# PS2toUSB.net
KiCad netlist of a schematic drawn in EasyEDA Pro
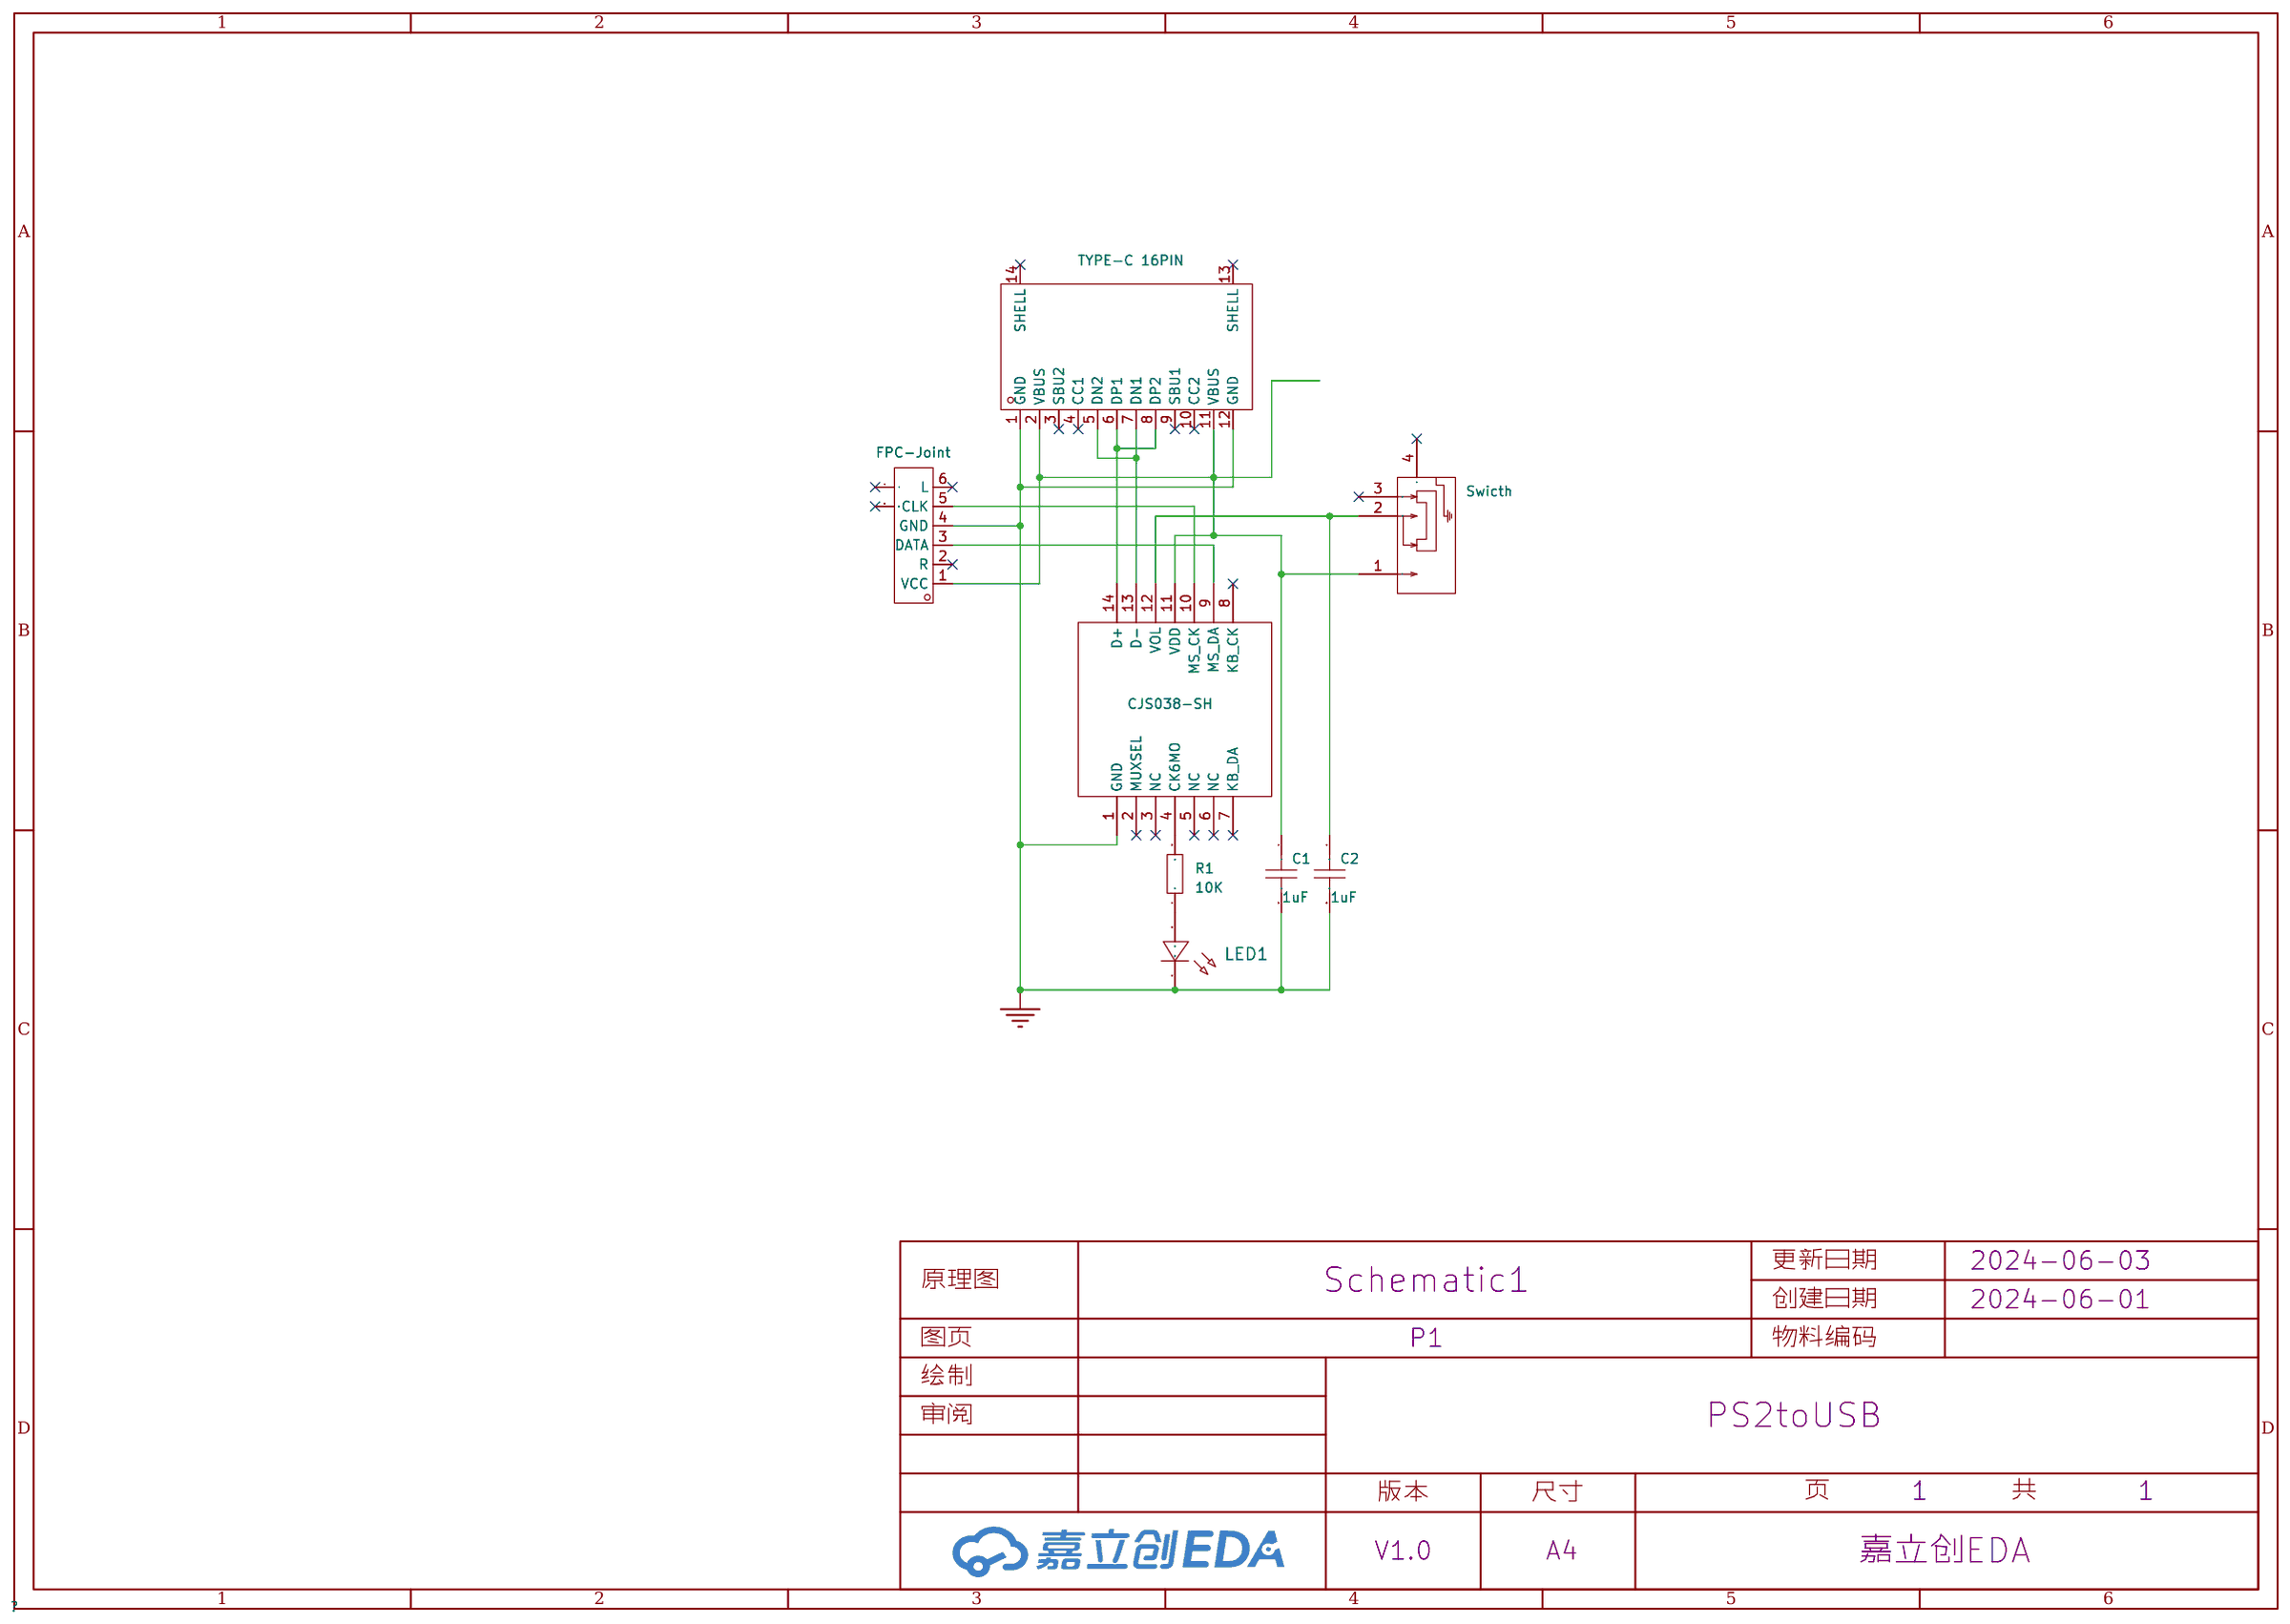
[diagram p0: schematic sheet]

(export (version "E")
  (design (tool "Eeschema 10.0.6"))
  (components
    (comp (ref "C1")
      (value "1uF")
      (footprint "easyedapro:C0603")
      (libsource (lib "easyedapro") (part "CapAcitance"))
    )
    (comp (ref "C2")
      (value "1uF")
      (footprint "easyedapro:C0603")
      (libsource (lib "easyedapro") (part "CapAcitance"))
    )
    (comp (ref "CJS038-SH")
      (value "~")
      (footprint "easyedapro:CJS038-SH")
      (description "协议转换芯片，将PS/2信号转换成USB信号")
      (libsource (lib "easyedapro") (part "CJS038-SH"))
    )
    (comp (ref "FPC-Joint")
      (value "VCC")
      (footprint "easyedapro:FPC-SMD_C47271")
      (description "锁定特性:抽屉式;触点类型:上接;触点数量:6P;间距:1mm;安装类型:卧贴;工作温度范围:-25°C~+85°C;")
      (fields (field (name "Manufacturer Part") "1.0-6P上接") (field (name "Manufacturer") "BOOMELE(博穆精密)"))
      (libsource (lib "easyedapro") (part "FPC 1.0mmpitch 6P Pull type Pick up"))
    )
    (comp (ref "LED1")
      (value "~")
      (footprint "easyedapro:LED_0603")
      (libsource (lib "easyedapro") (part "LED_R"))
    )
    (comp (ref "R1") (value "10K") (footprint "easyedapro:R0603") (libsource (lib "easyedapro") (part "电阻")))
    (comp (ref "SW1")
      (value "Swicth")
      (footprint "easyedapro:SW-TH_MSK12C02")
      (description "电路结构:单刀双掷;安装方式:卧贴;开关颜色:-;额定电流(DC):50mA;额定电压(DC):12V;额定电流(AC):-;额定电压(AC):-;机械寿命:1万次;")
      (fields (field (name "Manufacturer") "SHOU HAN(首韩)"))
      (libsource (lib "easyedapro") (part "MSK12C02"))
    )
    (comp (ref "USB1")
      (value "TYPE-C 16PIN")
      (footprint "easyedapro:USB-C-SMD_TYPE-C-6PIN-2MD-073")
      (description "连接器类型:Type-C;标准:-;公母:母;端口数量:1;触点数量:16P;安装方式:卧贴;额定电流 - 电源:5A;工作温度范围:-25°C~+85°C;")
      (fields (field (name "Manufacturer") "SHOU HAN(首韩)"))
      (libsource (lib "easyedapro") (part "TYPE-C 16PIN 2MD(073)"))
    )
  )
  (nets
    (net (code "1") (name "GND") (class "Default")
      (node (ref "C1") (pin "2") (pinfunction "2_2") (pintype "input"))
      (node (ref "C2") (pin "2") (pinfunction "2_2") (pintype "input"))
      (node (ref "CJS038-SH") (pin "1") (pinfunction "GND_1") (pintype "input"))
      (node (ref "FPC-Joint") (pin "4") (pinfunction "GND_4") (pintype "unspecified"))
      (node (ref "LED1") (pin "1") (pinfunction "C_1") (pintype "input"))
      (node (ref "USB1") (pin "1") (pinfunction "GND_1") (pintype "unspecified"))
      (node (ref "USB1") (pin "12") (pinfunction "GND_12") (pintype "unspecified"))
    )
    (net (code "2") (name "Net-(CJS038-SH-CK6MO)") (class "Default")
      (node (ref "CJS038-SH") (pin "4") (pinfunction "CK6MO_4") (pintype "input"))
      (node (ref "R1") (pin "2") (pinfunction "2_2") (pintype "input"))
    )
    (net (code "3") (name "Net-(CJS038-SH-D+)") (class "Default")
      (node (ref "CJS038-SH") (pin "14") (pinfunction "D+_14") (pintype "input"))
      (node (ref "USB1") (pin "6") (pinfunction "DP1_6") (pintype "unspecified"))
      (node (ref "USB1") (pin "8") (pinfunction "DP2_8") (pintype "unspecified"))
    )
    (net (code "4") (name "Net-(CJS038-SH-D-)") (class "Default")
      (node (ref "CJS038-SH") (pin "13") (pinfunction "D-_13") (pintype "input"))
      (node (ref "USB1") (pin "5") (pinfunction "DN2_5") (pintype "unspecified"))
      (node (ref "USB1") (pin "7") (pinfunction "DN1_7") (pintype "unspecified"))
    )
    (net (code "5") (name "Net-(CJS038-SH-MS_CK)") (class "Default")
      (node (ref "CJS038-SH") (pin "10") (pinfunction "MS_CK_10") (pintype "input"))
      (node (ref "FPC-Joint") (pin "5") (pinfunction "CLK_5") (pintype "unspecified"))
    )
    (net (code "6") (name "Net-(CJS038-SH-MS_DA)") (class "Default")
      (node (ref "CJS038-SH") (pin "9") (pinfunction "MS_DA_9") (pintype "input"))
      (node (ref "FPC-Joint") (pin "3") (pinfunction "DATA_3") (pintype "unspecified"))
    )
    (net (code "7") (name "Net-(CJS038-SH-VDD)") (class "Default")
      (node (ref "C1") (pin "1") (pinfunction "1_1") (pintype "input"))
      (node (ref "CJS038-SH") (pin "11") (pinfunction "VDD_11") (pintype "input"))
      (node (ref "FPC-Joint") (pin "1") (pinfunction "VCC_1") (pintype "unspecified"))
      (node (ref "SW1") (pin "1") (pinfunction "1_1") (pintype "unspecified"))
      (node (ref "USB1") (pin "11") (pinfunction "VBUS_11") (pintype "unspecified"))
      (node (ref "USB1") (pin "2") (pinfunction "VBUS_2") (pintype "unspecified"))
    )
    (net (code "8") (name "Net-(CJS038-SH-VOL)") (class "Default")
      (node (ref "C2") (pin "1") (pinfunction "1_1") (pintype "input"))
      (node (ref "CJS038-SH") (pin "12") (pinfunction "VOL_12") (pintype "input"))
      (node (ref "SW1") (pin "2") (pinfunction "2_2") (pintype "unspecified"))
    )
    (net (code "9") (name "Net-(LED1-A)") (class "Default")
      (node (ref "LED1") (pin "2") (pinfunction "A_2") (pintype "input"))
      (node (ref "R1") (pin "1") (pinfunction "1_1") (pintype "input"))
    )
    (net (code "10") (name "unconnected-(CJS038-SH-KB_CK-Pad8)") (class "Default")
      (node (ref "CJS038-SH") (pin "8") (pinfunction "KB_CK_8") (pintype "input+no_connect"))
    )
    (net (code "11") (name "unconnected-(CJS038-SH-KB_DA-Pad7)") (class "Default")
      (node (ref "CJS038-SH") (pin "7") (pinfunction "KB_DA_7") (pintype "input+no_connect"))
    )
    (net (code "12") (name "unconnected-(CJS038-SH-MUXSEL-Pad2)") (class "Default")
      (node (ref "CJS038-SH") (pin "2") (pinfunction "MUXSEL_2") (pintype "input+no_connect"))
    )
    (net (code "13") (name "unconnected-(CJS038-SH-NC-Pad3)") (class "Default")
      (node (ref "CJS038-SH") (pin "3") (pinfunction "NC_3") (pintype "input+no_connect"))
    )
    (net (code "14") (name "unconnected-(CJS038-SH-NC-Pad5)") (class "Default")
      (node (ref "CJS038-SH") (pin "5") (pinfunction "NC_5") (pintype "input+no_connect"))
    )
    (net (code "15") (name "unconnected-(CJS038-SH-NC-Pad6)") (class "Default")
      (node (ref "CJS038-SH") (pin "6") (pinfunction "NC_6") (pintype "input+no_connect"))
    )
    (net (code "16") (name "unconnected-(FPC-Joint-L-Pad6)") (class "Default")
      (node (ref "FPC-Joint") (pin "6") (pinfunction "L_6") (pintype "unspecified+no_connect"))
    )
    (net (code "17") (name "unconnected-(FPC-Joint-Pad7)") (class "Default")
      (node (ref "FPC-Joint") (pin "7") (pinfunction "7_7") (pintype "unspecified+no_connect"))
    )
    (net (code "18") (name "unconnected-(FPC-Joint-Pad8)") (class "Default")
      (node (ref "FPC-Joint") (pin "8") (pinfunction "8_8") (pintype "unspecified+no_connect"))
    )
    (net (code "19") (name "unconnected-(FPC-Joint-R-Pad2)") (class "Default")
      (node (ref "FPC-Joint") (pin "2") (pinfunction "R_2") (pintype "unspecified+no_connect"))
    )
    (net (code "20") (name "unconnected-(SW1-Pad3)") (class "Default")
      (node (ref "SW1") (pin "3") (pinfunction "3_3") (pintype "unspecified+no_connect"))
    )
    (net (code "21") (name "unconnected-(SW1-Pad4)") (class "Default")
      (node (ref "SW1") (pin "4") (pinfunction "4_4") (pintype "unspecified+no_connect"))
    )
    (net (code "22") (name "unconnected-(USB1-CC1-Pad4)") (class "Default")
      (node (ref "USB1") (pin "4") (pinfunction "CC1_4") (pintype "unspecified+no_connect"))
    )
    (net (code "23") (name "unconnected-(USB1-CC2-Pad10)") (class "Default")
      (node (ref "USB1") (pin "10") (pinfunction "CC2_10") (pintype "unspecified+no_connect"))
    )
    (net (code "24") (name "unconnected-(USB1-SBU1-Pad9)") (class "Default")
      (node (ref "USB1") (pin "9") (pinfunction "SBU1_9") (pintype "unspecified+no_connect"))
    )
    (net (code "25") (name "unconnected-(USB1-SBU2-Pad3)") (class "Default")
      (node (ref "USB1") (pin "3") (pinfunction "SBU2_3") (pintype "unspecified+no_connect"))
    )
    (net (code "26") (name "unconnected-(USB1-SHELL-Pad13)") (class "Default")
      (node (ref "USB1") (pin "13") (pinfunction "SHELL_13") (pintype "unspecified+no_connect"))
    )
    (net (code "27") (name "unconnected-(USB1-SHELL-Pad14)") (class "Default")
      (node (ref "USB1") (pin "14") (pinfunction "SHELL_14") (pintype "unspecified+no_connect"))
    )
  )
)
